# ProPrj_MSP3507__2025-07-14_10-12-05_2025.net
KiCad netlist of a schematic drawn in EasyEDA Pro
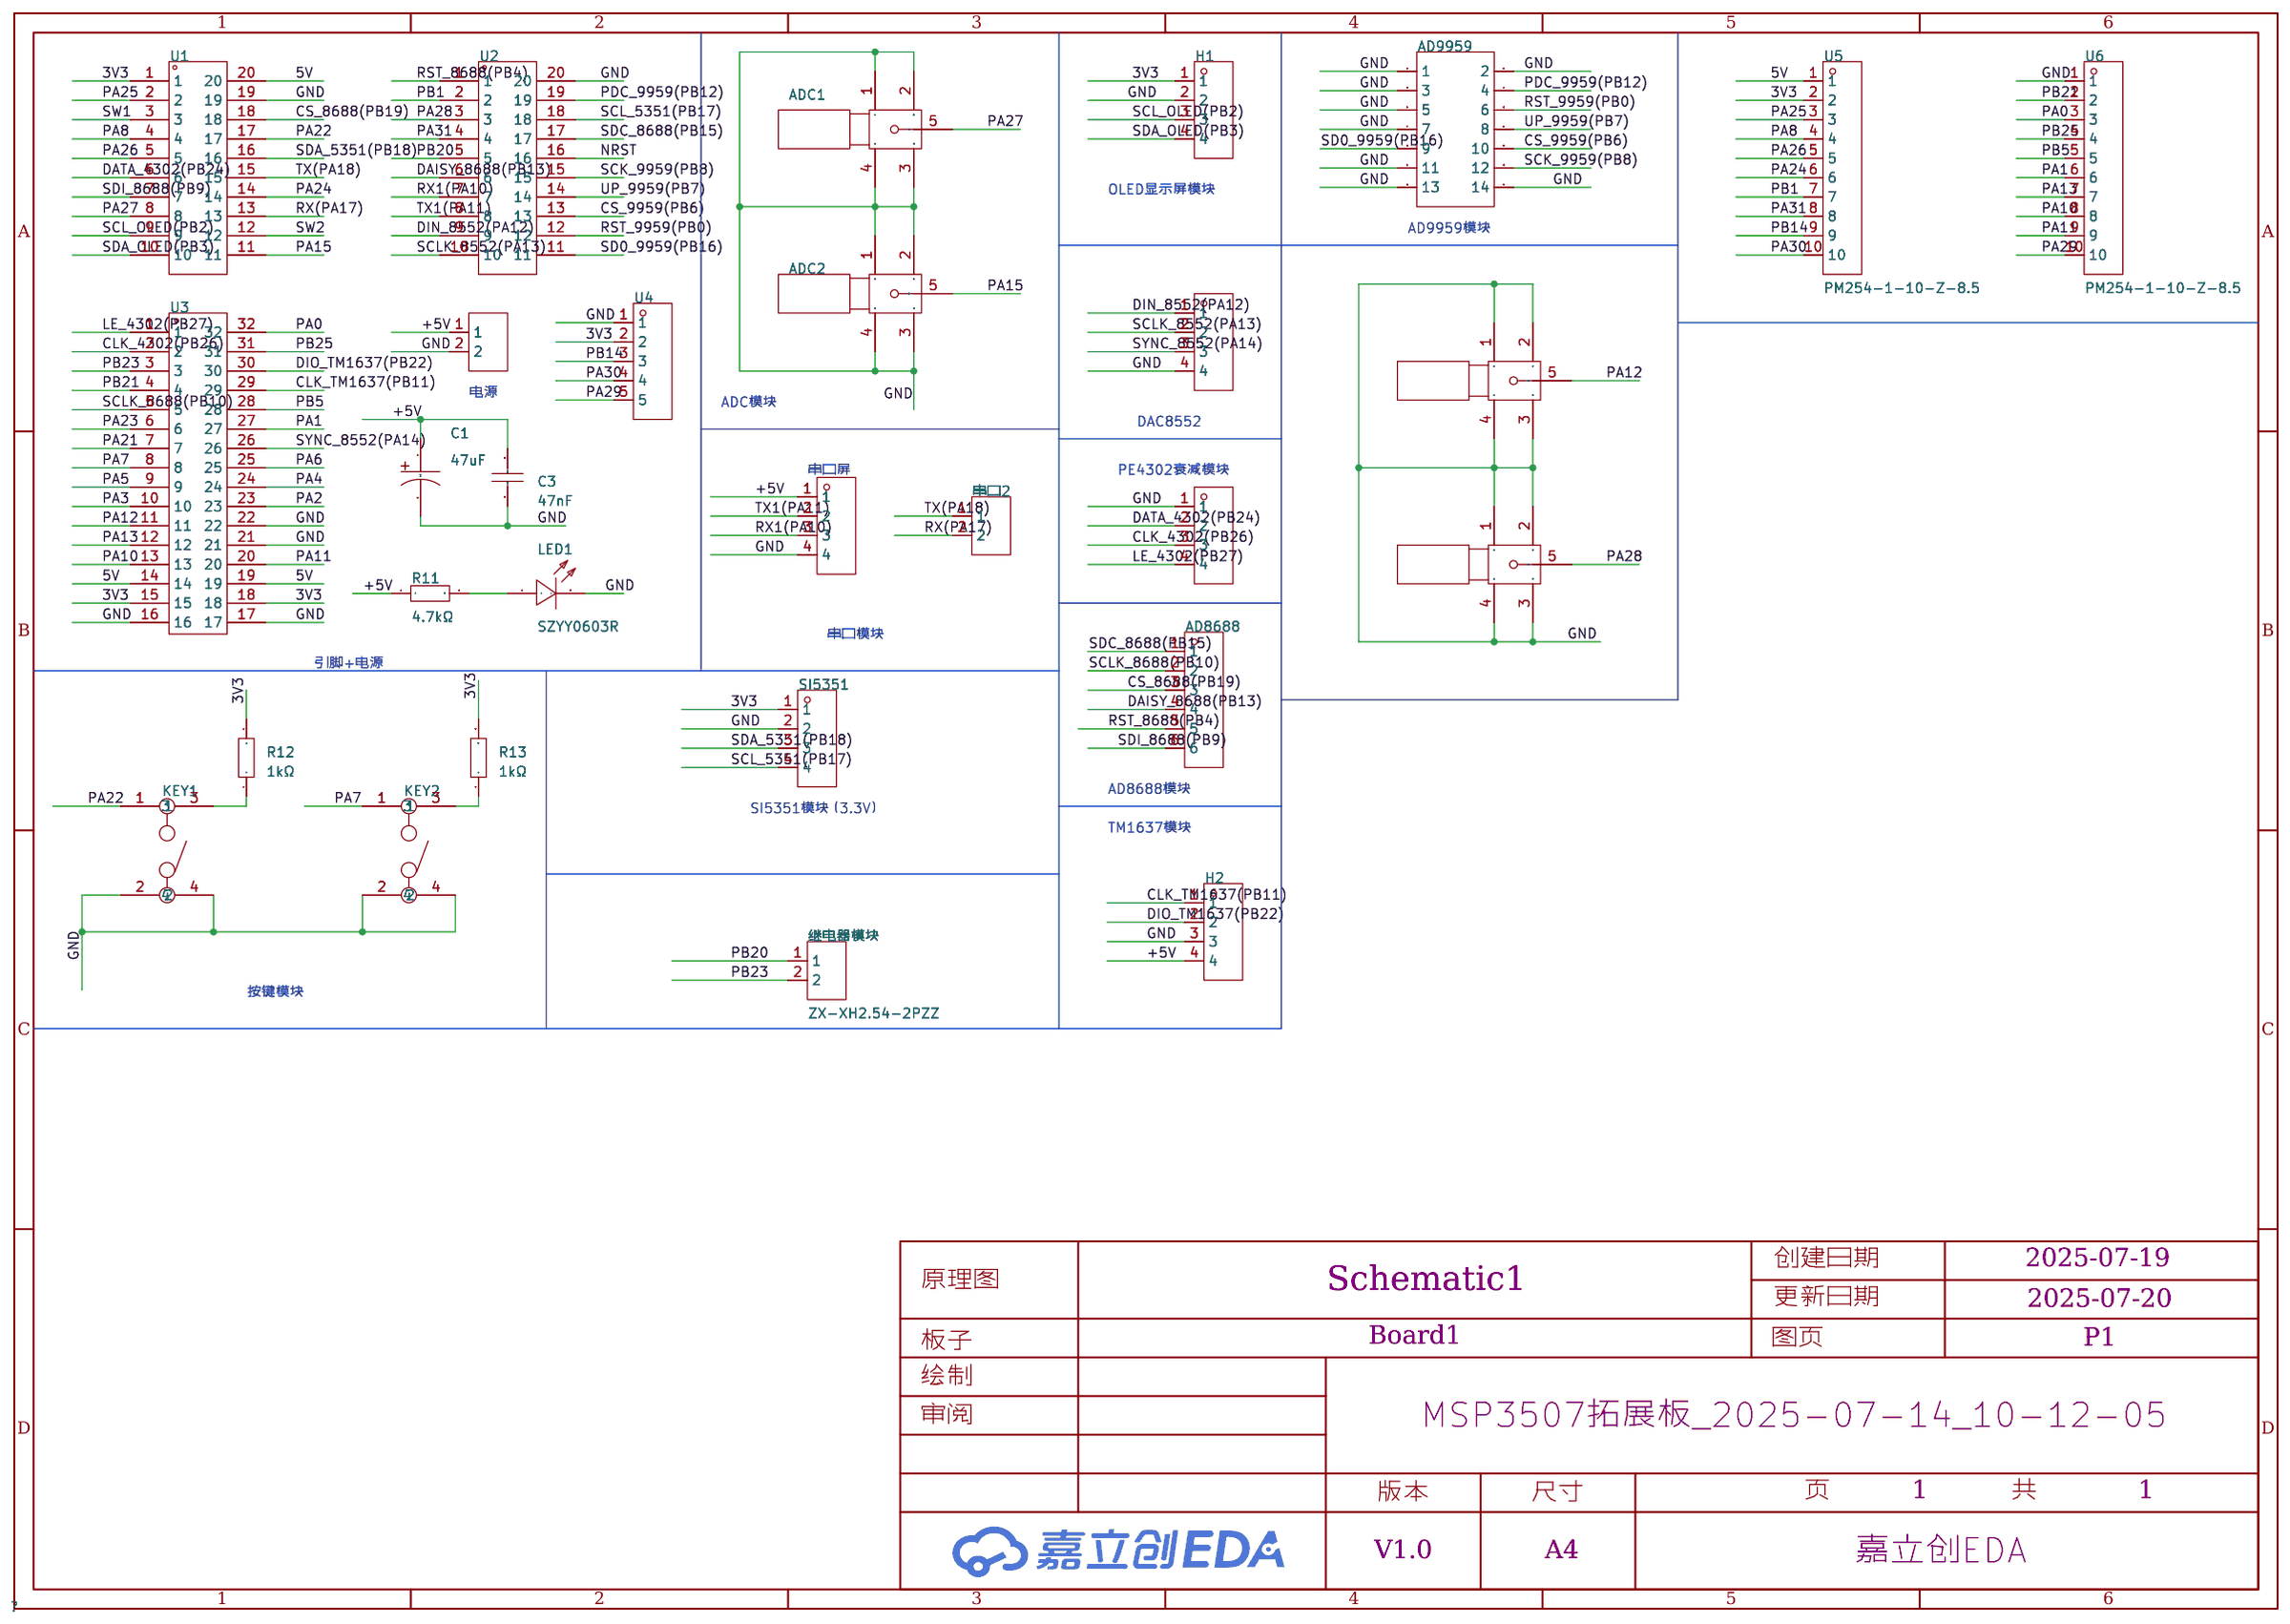
[diagram p0: schematic sheet]

(export (version "E")
  (design (tool "Eeschema 10.0.6"))
  (components
    (comp (ref "AD8688")
      (value "ZX-XH2.54-6PZZ")
      (footprint "easyedapro:CONN-TH_6P-P2.50_ZX-XH2.54-6PZZ")
      (fields (field (name "Manufacturer") "Megastar(兆星)"))
      (libsource (lib "easyedapro") (part "ZX-XH2.54-6PZZ"))
    )
    (comp (ref "AD9959")
      (value "2.54-2*7P简牛")
      (footprint "easyedapro:IDC-TH_14P-P2.54-V-R2-C7-S2.54")
      (description "连接器类型:简牛座;间距:2.54mm;结构:2x7P;封装形式:直插;行距:2.54mm;排数:2;每排PIN数:7;触头材质:黄铜;触头镀层:金;")
      (fields (field (name "Manufacturer") "BOOMELE(博穆精密)"))
      (libsource (lib "easyedapro") (part "HDR-IDC-2.54-2X7P"))
    )
    (comp (ref "ADC1")
      (value "BWSMA-KE-P001")
      (footprint "easyedapro:SMA-SMD_BWSMA-KE-P001")
      (description "连接器类型:板端;接口类型:内孔;端口数量:1;接口直径:5.2mm;接口长度/高度:-;频率-最大值:-;射频系列:SMA;阻抗:50Ω;样式:偏脚;工作温度范围:-;")
      (fields (field (name "Manufacturer") "BAT WIRELESS(蝙蝠无线)"))
      (libsource (lib "easyedapro") (part "BWSMA-KE-P001"))
    )
    (comp (ref "ADC2")
      (value "BWSMA-KE-P001")
      (footprint "easyedapro:SMA-SMD_BWSMA-KE-P001")
      (description "连接器类型:板端;接口类型:内孔;端口数量:1;接口直径:5.2mm;接口长度/高度:-;频率-最大值:-;射频系列:SMA;阻抗:50Ω;样式:偏脚;工作温度范围:-;")
      (fields (field (name "Manufacturer") "BAT WIRELESS(蝙蝠无线)"))
      (libsource (lib "easyedapro") (part "BWSMA-KE-P001"))
    )
    (comp (ref "C1")
      (value "47uF")
      (footprint "easyedapro:CAP-TH_BD5.0-P2.00-D0.8-FD")
      (description "容值:47uF;精度:±20%;额定电压:25V;纹波电流:250mA@100kHz;等效串联电阻(ESR):300mΩ@100kHz;")
      (fields
        (field (name "Manufacturer Part") "NXB25V47M5*11 2.5TP")
        (field (name "Manufacturer") "SAMYOUNG(韩国三莹)")
      )
      (libsource (lib "easyedapro") (part "NXB25VB47M5*11_2.5TP"))
    )
    (comp (ref "C3")
      (value "47nF")
      (footprint "easyedapro:C0805")
      (description "容值:47nF;精度:±10%;额定电压:50V;材质(温度系数):X7R;")
      (fields
        (field (name "Manufacturer Part") "CL21B473KBCNNNC")
        (field (name "Manufacturer") "SAMSUNG(三星)")
      )
      (libsource (lib "easyedapro") (part "CL21B473KBCNNNC"))
    )
    (comp (ref "DAC1")
      (value "BWSMA-KE-P001")
      (footprint "easyedapro:SMA-SMD_BWSMA-KE-P001")
      (description "连接器类型:板端;接口类型:内孔;端口数量:1;接口直径:5.2mm;接口长度/高度:-;频率-最大值:-;射频系列:SMA;阻抗:50Ω;样式:偏脚;工作温度范围:-;")
      (fields (field (name "Manufacturer") "BAT WIRELESS(蝙蝠无线)"))
      (libsource (lib "easyedapro") (part "BWSMA-KE-P001"))
    )
    (comp (ref "DAC2")
      (value "BWSMA-KE-P001")
      (footprint "easyedapro:SMA-SMD_BWSMA-KE-P001")
      (description "连接器类型:板端;接口类型:内孔;端口数量:1;接口直径:5.2mm;接口长度/高度:-;频率-最大值:-;射频系列:SMA;阻抗:50Ω;样式:偏脚;工作温度范围:-;")
      (fields (field (name "Manufacturer") "BAT WIRELESS(蝙蝠无线)"))
      (libsource (lib "easyedapro") (part "BWSMA-KE-P001"))
    )
    (comp (ref "H1")
      (value "~")
      (footprint "easyedapro:HDR-TH_4P-P2.54-V-F")
      (libsource (lib "easyedapro") (part "2.54-1*4P母"))
    )
    (comp (ref "H2")
      (value "~")
      (footprint "easyedapro:HDR-TH_4P-P2.54-V-F")
      (libsource (lib "easyedapro") (part "2.54-1*4P母"))
    )
    (comp (ref "KEY1")
      (value "~")
      (footprint "easyedapro:4角直插式开关")
      (description "4.5*4.5*3.8")
      (libsource (lib "easyedapro") (part "4角直插式开关"))
    )
    (comp (ref "KEY2")
      (value "~")
      (footprint "easyedapro:4角直插式开关")
      (description "4.5*4.5*3.8")
      (libsource (lib "easyedapro") (part "4角直插式开关"))
    )
    (comp (ref "LED1")
      (value "SZYY0603R")
      (footprint "easyedapro:LED0603-R-RD")
      (fields (field (name "Manufacturer") "yongyu(永裕光电)"))
      (libsource (lib "easyedapro") (part "SZYY0603R"))
    )
    (comp (ref "OLED显示屏模块1")
      (value "ZX-XH2.54-4PZZ")
      (footprint "easyedapro:CONN-TH_4P-P2.50_4PIN")
      (fields (field (name "Manufacturer") "Megastar(兆星)"))
      (libsource (lib "easyedapro") (part "ZX-XH2.54-4PZZ"))
    )
    (comp (ref "OLED显示屏模块2")
      (value "ZX-XH2.54-4PZZ")
      (footprint "easyedapro:CONN-TH_4P-P2.50_4PIN")
      (fields (field (name "Manufacturer") "Megastar(兆星)"))
      (libsource (lib "easyedapro") (part "ZX-XH2.54-4PZZ"))
    )
    (comp (ref "OLED显示屏模块3")
      (value "ZX-XH2.54-4PZZ")
      (footprint "easyedapro:CONN-TH_4P-P2.50_4PIN")
      (fields (field (name "Manufacturer") "Megastar(兆星)"))
      (libsource (lib "easyedapro") (part "ZX-XH2.54-4PZZ"))
    )
    (comp (ref "R11")
      (value "4.7kΩ")
      (footprint "easyedapro:R0805")
      (description "电阻类型:厚膜电阻;阻值:4.7kΩ;精度:±1%;功率:125mW;最大工作电压:150V;温度系数:±100ppm/°C;")
      (fields
        (field (name "Manufacturer Part") "0805W8F4701T5E")
        (field (name "Manufacturer") "UNI-ROYAL(厚声)")
      )
      (libsource (lib "easyedapro") (part "0805W8F4701T5E"))
    )
    (comp (ref "R12")
      (value "1kΩ")
      (footprint "easyedapro:R0805")
      (description "电阻类型:厚膜电阻;阻值:1kΩ;精度:±1%;功率:125mW;温度系数:±100ppm/°C;最大工作电压:150V;工作温度范围:-55°C~+155°C;")
      (fields
        (field (name "Manufacturer Part") "0805W8F1001T5E")
        (field (name "Manufacturer") "UNI-ROYAL(厚声)")
      )
      (libsource (lib "easyedapro") (part "0805W8F1001T5E"))
    )
    (comp (ref "R13")
      (value "1kΩ")
      (footprint "easyedapro:R0805")
      (description "电阻类型:厚膜电阻;阻值:1kΩ;精度:±1%;功率:125mW;温度系数:±100ppm/°C;最大工作电压:150V;工作温度范围:-55°C~+155°C;")
      (fields
        (field (name "Manufacturer Part") "0805W8F1001T5E")
        (field (name "Manufacturer") "UNI-ROYAL(厚声)")
      )
      (libsource (lib "easyedapro") (part "0805W8F1001T5E"))
    )
    (comp (ref "SI5351")
      (value "ZX-XH2.54-4PZZ")
      (footprint "easyedapro:CONN-TH_4P-P2.50_4PIN")
      (fields (field (name "Manufacturer") "Megastar(兆星)"))
      (libsource (lib "easyedapro") (part "ZX-XH2.54-4PZZ"))
    )
    (comp (ref "U1")
      (value "~")
      (footprint "easyedapro:2*10Pin排针")
      (description "2.54")
      (libsource (lib "easyedapro") (part "2*10Pin排针"))
    )
    (comp (ref "U2")
      (value "~")
      (footprint "easyedapro:2*10Pin排针")
      (description "2.54")
      (libsource (lib "easyedapro") (part "2*10Pin排针"))
    )
    (comp (ref "U3")
      (value "~")
      (footprint "easyedapro:2*16Pin排针")
      (description "2.54")
      (libsource (lib "easyedapro") (part "2*16Pin排针"))
    )
    (comp (ref "U4")
      (value "PZ254V-11-05P")
      (footprint "easyedapro:HDR-TH_5P-P2.54-V-M")
      (fields (field (name "Manufacturer") "XFCN(兴飞)"))
      (libsource (lib "easyedapro") (part "PZ254V-11-05P"))
    )
    (comp (ref "U5")
      (value "PM254-1-10-Z-8.5")
      (footprint "easyedapro:HDR-TH_10P-P2.54-V-F")
      (fields (field (name "Manufacturer") "HCTL(华灿天禄)"))
      (libsource (lib "easyedapro") (part "PM254-1-10-Z-8.5"))
    )
    (comp (ref "U6")
      (value "PM254-1-10-Z-8.5")
      (footprint "easyedapro:HDR-TH_10P-P2.54-V-F")
      (fields (field (name "Manufacturer") "HCTL(华灿天禄)"))
      (libsource (lib "easyedapro") (part "PM254-1-10-Z-8.5"))
    )
    (comp (ref "串口1")
      (value "ZX-XH2.54-2PZZ")
      (footprint "easyedapro:CONN-TH_2P-P2.50_HX25003-2A")
      (fields (field (name "Manufacturer") "Megastar(兆星)"))
      (libsource (lib "easyedapro") (part "ZX-XH2.54-2PZZ"))
    )
    (comp (ref "串口2")
      (value "ZX-XH2.54-2PZZ")
      (footprint "easyedapro:CONN-TH_2P-P2.50_HX25003-2A")
      (fields (field (name "Manufacturer") "Megastar(兆星)"))
      (libsource (lib "easyedapro") (part "ZX-XH2.54-2PZZ"))
    )
    (comp (ref "继电器模块")
      (value "ZX-XH2.54-2PZZ")
      (footprint "easyedapro:CONN-TH_2P-P2.50_HX25003-2A")
      (fields (field (name "Manufacturer") "Megastar(兆星)"))
      (libsource (lib "easyedapro") (part "ZX-XH2.54-2PZZ"))
    )
  )
  (nets
    (net (code "1") (name "/+5V") (class "Default")
      (node (ref "C1") (pin "1") (pinfunction "1_1") (pintype "unspecified"))
      (node (ref "C3") (pin "2") (pinfunction "2_2") (pintype "input"))
      (node (ref "H2") (pin "4") (pinfunction "4_4") (pintype "unspecified"))
      (node (ref "OLED显示屏模块2") (pin "1") (pinfunction "1_1") (pintype "unspecified"))
      (node (ref "R11") (pin "1") (pinfunction "1_1") (pintype "input"))
      (node (ref "串口1") (pin "1") (pinfunction "1_1") (pintype "unspecified"))
    )
    (net (code "2") (name "/3V3") (class "Default")
      (node (ref "H1") (pin "1") (pinfunction "1_1") (pintype "unspecified"))
      (node (ref "R12") (pin "2") (pinfunction "2_2") (pintype "input"))
      (node (ref "R13") (pin "2") (pinfunction "2_2") (pintype "input"))
      (node (ref "SI5351") (pin "1") (pinfunction "1_1") (pintype "unspecified"))
      (node (ref "U1") (pin "1") (pinfunction "1_1") (pintype "input"))
      (node (ref "U3") (pin "15") (pinfunction "15_15") (pintype "input"))
      (node (ref "U3") (pin "18") (pinfunction "18_18") (pintype "input"))
      (node (ref "U4") (pin "2") (pinfunction "2_2") (pintype "input"))
      (node (ref "U5") (pin "2") (pinfunction "2_2") (pintype "unspecified"))
    )
    (net (code "3") (name "/5V") (class "Default")
      (node (ref "U1") (pin "20") (pinfunction "20_20") (pintype "input"))
      (node (ref "U3") (pin "14") (pinfunction "14_14") (pintype "input"))
      (node (ref "U3") (pin "19") (pinfunction "19_19") (pintype "input"))
      (node (ref "U5") (pin "1") (pinfunction "1_1") (pintype "unspecified"))
    )
    (net (code "4") (name "/CLK_4302(PB26)") (class "Default")
      (node (ref "OLED显示屏模块1") (pin "3") (pinfunction "3_3") (pintype "unspecified"))
      (node (ref "U3") (pin "2") (pinfunction "2_2") (pintype "input"))
    )
    (net (code "5") (name "/CLK_TM1637(PB11)") (class "Default")
      (node (ref "H2") (pin "1") (pinfunction "1_1") (pintype "unspecified"))
      (node (ref "U3") (pin "29") (pinfunction "29_29") (pintype "input"))
    )
    (net (code "6") (name "/CS_8688(PB19)") (class "Default")
      (node (ref "AD8688") (pin "3") (pinfunction "3_3") (pintype "unspecified"))
      (node (ref "U1") (pin "18") (pinfunction "18_18") (pintype "input"))
    )
    (net (code "7") (name "/CS_9959(PB6)") (class "Default")
      (node (ref "AD9959") (pin "10") (pinfunction "10_10") (pintype "unspecified"))
      (node (ref "U2") (pin "13") (pinfunction "13_13") (pintype "input"))
    )
    (net (code "8") (name "/DAISY_8688(PB13)") (class "Default")
      (node (ref "AD8688") (pin "4") (pinfunction "4_4") (pintype "unspecified"))
      (node (ref "U2") (pin "6") (pinfunction "6_6") (pintype "input"))
    )
    (net (code "9") (name "/DATA_4302(PB24)") (class "Default")
      (node (ref "OLED显示屏模块1") (pin "2") (pinfunction "2_2") (pintype "unspecified"))
      (node (ref "U1") (pin "6") (pinfunction "6_6") (pintype "input"))
    )
    (net (code "10") (name "/DIN_8552(PA12)") (class "Default")
      (node (ref "OLED显示屏模块3") (pin "1") (pinfunction "1_1") (pintype "unspecified"))
      (node (ref "U2") (pin "9") (pinfunction "9_9") (pintype "input"))
    )
    (net (code "11") (name "/DIO_TM1637(PB22)") (class "Default")
      (node (ref "H2") (pin "2") (pinfunction "2_2") (pintype "unspecified"))
      (node (ref "U3") (pin "30") (pinfunction "30_30") (pintype "input"))
    )
    (net (code "12") (name "/GND") (class "Default")
      (node (ref "AD9959") (pin "1") (pinfunction "1_1") (pintype "unspecified"))
      (node (ref "AD9959") (pin "11") (pinfunction "11_11") (pintype "unspecified"))
      (node (ref "AD9959") (pin "13") (pinfunction "13_13") (pintype "unspecified"))
      (node (ref "AD9959") (pin "14") (pinfunction "14_14") (pintype "unspecified"))
      (node (ref "AD9959") (pin "2") (pinfunction "2_2") (pintype "unspecified"))
      (node (ref "AD9959") (pin "3") (pinfunction "3_3") (pintype "unspecified"))
      (node (ref "AD9959") (pin "5") (pinfunction "5_5") (pintype "unspecified"))
      (node (ref "AD9959") (pin "7") (pinfunction "7_7") (pintype "unspecified"))
      (node (ref "ADC1") (pin "1") (pinfunction "1_1") (pintype "unspecified"))
      (node (ref "ADC1") (pin "2") (pinfunction "2_2") (pintype "unspecified"))
      (node (ref "ADC1") (pin "3") (pinfunction "3_3") (pintype "unspecified"))
      (node (ref "ADC1") (pin "4") (pinfunction "4_4") (pintype "unspecified"))
      (node (ref "ADC2") (pin "1") (pinfunction "1_1") (pintype "unspecified"))
      (node (ref "ADC2") (pin "2") (pinfunction "2_2") (pintype "unspecified"))
      (node (ref "ADC2") (pin "3") (pinfunction "3_3") (pintype "unspecified"))
      (node (ref "ADC2") (pin "4") (pinfunction "4_4") (pintype "unspecified"))
      (node (ref "C1") (pin "2") (pinfunction "2_2") (pintype "unspecified"))
      (node (ref "C3") (pin "1") (pinfunction "1_1") (pintype "input"))
      (node (ref "DAC1") (pin "1") (pinfunction "1_1") (pintype "unspecified"))
      (node (ref "DAC1") (pin "2") (pinfunction "2_2") (pintype "unspecified"))
      (node (ref "DAC1") (pin "3") (pinfunction "3_3") (pintype "unspecified"))
      (node (ref "DAC1") (pin "4") (pinfunction "4_4") (pintype "unspecified"))
      (node (ref "DAC2") (pin "1") (pinfunction "1_1") (pintype "unspecified"))
      (node (ref "DAC2") (pin "2") (pinfunction "2_2") (pintype "unspecified"))
      (node (ref "DAC2") (pin "3") (pinfunction "3_3") (pintype "unspecified"))
      (node (ref "DAC2") (pin "4") (pinfunction "4_4") (pintype "unspecified"))
      (node (ref "H1") (pin "2") (pinfunction "2_2") (pintype "unspecified"))
      (node (ref "H2") (pin "3") (pinfunction "3_3") (pintype "unspecified"))
      (node (ref "KEY1") (pin "2") (pinfunction "2_2") (pintype "input"))
      (node (ref "KEY1") (pin "4") (pinfunction "4_4") (pintype "input"))
      (node (ref "KEY2") (pin "2") (pinfunction "2_2") (pintype "input"))
      (node (ref "KEY2") (pin "4") (pinfunction "4_4") (pintype "input"))
      (node (ref "LED1") (pin "2") (pinfunction "-_2") (pintype "unspecified"))
      (node (ref "OLED显示屏模块1") (pin "1") (pinfunction "1_1") (pintype "unspecified"))
      (node (ref "OLED显示屏模块2") (pin "4") (pinfunction "4_4") (pintype "unspecified"))
      (node (ref "OLED显示屏模块3") (pin "4") (pinfunction "4_4") (pintype "unspecified"))
      (node (ref "SI5351") (pin "2") (pinfunction "2_2") (pintype "unspecified"))
      (node (ref "U1") (pin "19") (pinfunction "19_19") (pintype "input"))
      (node (ref "U2") (pin "20") (pinfunction "20_20") (pintype "input"))
      (node (ref "U3") (pin "16") (pinfunction "16_16") (pintype "input"))
      (node (ref "U3") (pin "17") (pinfunction "17_17") (pintype "input"))
      (node (ref "U3") (pin "21") (pinfunction "21_21") (pintype "input"))
      (node (ref "U3") (pin "22") (pinfunction "22_22") (pintype "input"))
      (node (ref "U4") (pin "1") (pinfunction "1_1") (pintype "input"))
      (node (ref "U6") (pin "1") (pinfunction "1_1") (pintype "unspecified"))
      (node (ref "串口1") (pin "2") (pinfunction "2_2") (pintype "unspecified"))
    )
    (net (code "13") (name "/LE_4302(PB27)") (class "Default")
      (node (ref "OLED显示屏模块1") (pin "4") (pinfunction "4_4") (pintype "unspecified"))
      (node (ref "U3") (pin "1") (pinfunction "1_1") (pintype "input"))
    )
    (net (code "14") (name "/NRST") (class "Default")
      (node (ref "U2") (pin "16") (pinfunction "16_16") (pintype "input"))
    )
    (net (code "15") (name "/PA0") (class "Default")
      (node (ref "U3") (pin "32") (pinfunction "32_32") (pintype "input"))
      (node (ref "U6") (pin "3") (pinfunction "3_3") (pintype "unspecified"))
    )
    (net (code "16") (name "/PA1") (class "Default")
      (node (ref "U3") (pin "27") (pinfunction "27_27") (pintype "input"))
      (node (ref "U6") (pin "6") (pinfunction "6_6") (pintype "unspecified"))
    )
    (net (code "17") (name "/PA2") (class "Default")
      (node (ref "U3") (pin "23") (pinfunction "23_23") (pintype "input"))
    )
    (net (code "18") (name "/PA3") (class "Default")
      (node (ref "U3") (pin "10") (pinfunction "10_10") (pintype "input"))
    )
    (net (code "19") (name "/PA4") (class "Default")
      (node (ref "U3") (pin "24") (pinfunction "24_24") (pintype "input"))
    )
    (net (code "20") (name "/PA5") (class "Default")
      (node (ref "U3") (pin "9") (pinfunction "9_9") (pintype "input"))
    )
    (net (code "21") (name "/PA6") (class "Default")
      (node (ref "U3") (pin "25") (pinfunction "25_25") (pintype "input"))
    )
    (net (code "22") (name "/PA7") (class "Default")
      (node (ref "KEY2") (pin "1") (pinfunction "1_1") (pintype "input"))
      (node (ref "U3") (pin "8") (pinfunction "8_8") (pintype "input"))
    )
    (net (code "23") (name "/PA8") (class "Default")
      (node (ref "U1") (pin "4") (pinfunction "4_4") (pintype "input"))
      (node (ref "U5") (pin "4") (pinfunction "4_4") (pintype "unspecified"))
    )
    (net (code "24") (name "/PA10") (class "Default")
      (node (ref "U3") (pin "13") (pinfunction "13_13") (pintype "input"))
      (node (ref "U6") (pin "8") (pinfunction "8_8") (pintype "unspecified"))
    )
    (net (code "25") (name "/PA11") (class "Default")
      (node (ref "U3") (pin "20") (pinfunction "20_20") (pintype "input"))
      (node (ref "U6") (pin "9") (pinfunction "9_9") (pintype "unspecified"))
    )
    (net (code "26") (name "/PA12") (class "Default")
      (node (ref "DAC1") (pin "5") (pinfunction "5_5") (pintype "unspecified"))
      (node (ref "U3") (pin "11") (pinfunction "11_11") (pintype "input"))
    )
    (net (code "27") (name "/PA13") (class "Default")
      (node (ref "U3") (pin "12") (pinfunction "12_12") (pintype "input"))
      (node (ref "U6") (pin "7") (pinfunction "7_7") (pintype "unspecified"))
    )
    (net (code "28") (name "/PA15") (class "Default")
      (node (ref "ADC2") (pin "5") (pinfunction "5_5") (pintype "unspecified"))
      (node (ref "U1") (pin "11") (pinfunction "11_11") (pintype "input"))
    )
    (net (code "29") (name "/PA21") (class "Default")
      (node (ref "U3") (pin "7") (pinfunction "7_7") (pintype "input"))
    )
    (net (code "30") (name "/PA22") (class "Default")
      (node (ref "KEY1") (pin "1") (pinfunction "1_1") (pintype "input"))
      (node (ref "U1") (pin "17") (pinfunction "17_17") (pintype "input"))
    )
    (net (code "31") (name "/PA23") (class "Default")
      (node (ref "U3") (pin "6") (pinfunction "6_6") (pintype "input"))
    )
    (net (code "32") (name "/PA24") (class "Default")
      (node (ref "U1") (pin "14") (pinfunction "14_14") (pintype "input"))
      (node (ref "U5") (pin "6") (pinfunction "6_6") (pintype "unspecified"))
    )
    (net (code "33") (name "/PA25") (class "Default")
      (node (ref "U1") (pin "2") (pinfunction "2_2") (pintype "input"))
      (node (ref "U5") (pin "3") (pinfunction "3_3") (pintype "unspecified"))
    )
    (net (code "34") (name "/PA26") (class "Default")
      (node (ref "U1") (pin "5") (pinfunction "5_5") (pintype "input"))
      (node (ref "U5") (pin "5") (pinfunction "5_5") (pintype "unspecified"))
    )
    (net (code "35") (name "/PA27") (class "Default")
      (node (ref "ADC1") (pin "5") (pinfunction "5_5") (pintype "unspecified"))
      (node (ref "U1") (pin "8") (pinfunction "8_8") (pintype "input"))
    )
    (net (code "36") (name "/PA28") (class "Default")
      (node (ref "DAC2") (pin "5") (pinfunction "5_5") (pintype "unspecified"))
      (node (ref "U2") (pin "3") (pinfunction "3_3") (pintype "input"))
    )
    (net (code "37") (name "/PA29") (class "Default")
      (node (ref "U4") (pin "5") (pinfunction "5_5") (pintype "input"))
      (node (ref "U6") (pin "10") (pinfunction "10_10") (pintype "unspecified"))
    )
    (net (code "38") (name "/PA30") (class "Default")
      (node (ref "U4") (pin "4") (pinfunction "4_4") (pintype "input"))
      (node (ref "U5") (pin "10") (pinfunction "10_10") (pintype "unspecified"))
    )
    (net (code "39") (name "/PA31") (class "Default")
      (node (ref "U2") (pin "4") (pinfunction "4_4") (pintype "input"))
      (node (ref "U5") (pin "8") (pinfunction "8_8") (pintype "unspecified"))
    )
    (net (code "40") (name "/PB1") (class "Default")
      (node (ref "U2") (pin "2") (pinfunction "2_2") (pintype "input"))
      (node (ref "U5") (pin "7") (pinfunction "7_7") (pintype "unspecified"))
    )
    (net (code "41") (name "/PB5") (class "Default")
      (node (ref "U3") (pin "28") (pinfunction "28_28") (pintype "input"))
      (node (ref "U6") (pin "5") (pinfunction "5_5") (pintype "unspecified"))
    )
    (net (code "42") (name "/PB14") (class "Default")
      (node (ref "U4") (pin "3") (pinfunction "3_3") (pintype "input"))
      (node (ref "U5") (pin "9") (pinfunction "9_9") (pintype "unspecified"))
    )
    (net (code "43") (name "/PB20") (class "Default")
      (node (ref "U2") (pin "5") (pinfunction "5_5") (pintype "input"))
      (node (ref "继电器模块") (pin "1") (pinfunction "1_1") (pintype "unspecified"))
    )
    (net (code "44") (name "/PB21") (class "Default")
      (node (ref "U3") (pin "4") (pinfunction "4_4") (pintype "input"))
      (node (ref "U6") (pin "2") (pinfunction "2_2") (pintype "unspecified"))
    )
    (net (code "45") (name "/PB23") (class "Default")
      (node (ref "U3") (pin "3") (pinfunction "3_3") (pintype "input"))
      (node (ref "继电器模块") (pin "2") (pinfunction "2_2") (pintype "unspecified"))
    )
    (net (code "46") (name "/PB25") (class "Default")
      (node (ref "U3") (pin "31") (pinfunction "31_31") (pintype "input"))
      (node (ref "U6") (pin "4") (pinfunction "4_4") (pintype "unspecified"))
    )
    (net (code "47") (name "/PDC_9959(PB12)") (class "Default")
      (node (ref "AD9959") (pin "4") (pinfunction "4_4") (pintype "unspecified"))
      (node (ref "U2") (pin "19") (pinfunction "19_19") (pintype "input"))
    )
    (net (code "48") (name "/RST_8688(PB4)") (class "Default")
      (node (ref "AD8688") (pin "5") (pinfunction "5_5") (pintype "unspecified"))
      (node (ref "U2") (pin "1") (pinfunction "1_1") (pintype "input"))
    )
    (net (code "49") (name "/RST_9959(PB0)") (class "Default")
      (node (ref "AD9959") (pin "6") (pinfunction "6_6") (pintype "unspecified"))
      (node (ref "U2") (pin "12") (pinfunction "12_12") (pintype "input"))
    )
    (net (code "50") (name "/RX(PA17)") (class "Default")
      (node (ref "U1") (pin "13") (pinfunction "13_13") (pintype "input"))
      (node (ref "串口2") (pin "2") (pinfunction "2_2") (pintype "unspecified"))
    )
    (net (code "51") (name "/RX1(PA10)") (class "Default")
      (node (ref "OLED显示屏模块2") (pin "3") (pinfunction "3_3") (pintype "unspecified"))
      (node (ref "U2") (pin "7") (pinfunction "7_7") (pintype "input"))
    )
    (net (code "52") (name "/SCK_9959(PB8)") (class "Default")
      (node (ref "AD9959") (pin "12") (pinfunction "12_12") (pintype "unspecified"))
      (node (ref "U2") (pin "15") (pinfunction "15_15") (pintype "input"))
    )
    (net (code "53") (name "/SCLK_8552(PA13)") (class "Default")
      (node (ref "OLED显示屏模块3") (pin "2") (pinfunction "2_2") (pintype "unspecified"))
      (node (ref "U2") (pin "10") (pinfunction "10_10") (pintype "input"))
    )
    (net (code "54") (name "/SCLK_8688(PB10)") (class "Default")
      (node (ref "AD8688") (pin "2") (pinfunction "2_2") (pintype "unspecified"))
      (node (ref "U3") (pin "5") (pinfunction "5_5") (pintype "input"))
    )
    (net (code "55") (name "/SCL_5351(PB17)") (class "Default")
      (node (ref "SI5351") (pin "4") (pinfunction "4_4") (pintype "unspecified"))
      (node (ref "U2") (pin "18") (pinfunction "18_18") (pintype "input"))
    )
    (net (code "56") (name "/SCL_OLED(PB2)") (class "Default")
      (node (ref "H1") (pin "3") (pinfunction "3_3") (pintype "unspecified"))
      (node (ref "U1") (pin "9") (pinfunction "9_9") (pintype "input"))
    )
    (net (code "57") (name "/SD0_9959(PB16)") (class "Default")
      (node (ref "AD9959") (pin "9") (pinfunction "9_9") (pintype "unspecified"))
      (node (ref "U2") (pin "11") (pinfunction "11_11") (pintype "input"))
    )
    (net (code "58") (name "/SDA_5351(PB18)") (class "Default")
      (node (ref "SI5351") (pin "3") (pinfunction "3_3") (pintype "unspecified"))
      (node (ref "U1") (pin "16") (pinfunction "16_16") (pintype "input"))
    )
    (net (code "59") (name "/SDA_OLED(PB3)") (class "Default")
      (node (ref "H1") (pin "4") (pinfunction "4_4") (pintype "unspecified"))
      (node (ref "U1") (pin "10") (pinfunction "10_10") (pintype "input"))
    )
    (net (code "60") (name "/SDC_8688(PB15)") (class "Default")
      (node (ref "AD8688") (pin "1") (pinfunction "1_1") (pintype "unspecified"))
      (node (ref "U2") (pin "17") (pinfunction "17_17") (pintype "input"))
    )
    (net (code "61") (name "/SDI_8688(PB9)") (class "Default")
      (node (ref "AD8688") (pin "6") (pinfunction "6_6") (pintype "unspecified"))
      (node (ref "U1") (pin "7") (pinfunction "7_7") (pintype "input"))
    )
    (net (code "62") (name "/SW1") (class "Default")
      (node (ref "U1") (pin "3") (pinfunction "3_3") (pintype "input"))
    )
    (net (code "63") (name "/SW2") (class "Default")
      (node (ref "U1") (pin "12") (pinfunction "12_12") (pintype "input"))
    )
    (net (code "64") (name "/SYNC_8552(PA14)") (class "Default")
      (node (ref "OLED显示屏模块3") (pin "3") (pinfunction "3_3") (pintype "unspecified"))
      (node (ref "U3") (pin "26") (pinfunction "26_26") (pintype "input"))
    )
    (net (code "65") (name "/TX(PA18)") (class "Default")
      (node (ref "U1") (pin "15") (pinfunction "15_15") (pintype "input"))
      (node (ref "串口2") (pin "1") (pinfunction "1_1") (pintype "unspecified"))
    )
    (net (code "66") (name "/TX1(PA11)") (class "Default")
      (node (ref "OLED显示屏模块2") (pin "2") (pinfunction "2_2") (pintype "unspecified"))
      (node (ref "U2") (pin "8") (pinfunction "8_8") (pintype "input"))
    )
    (net (code "67") (name "/UP_9959(PB7)") (class "Default")
      (node (ref "AD9959") (pin "8") (pinfunction "8_8") (pintype "unspecified"))
      (node (ref "U2") (pin "14") (pinfunction "14_14") (pintype "input"))
    )
    (net (code "68") (name "Net-(KEY1-Pad3)") (class "Default")
      (node (ref "KEY1") (pin "3") (pinfunction "3_3") (pintype "input"))
      (node (ref "R12") (pin "1") (pinfunction "1_1") (pintype "input"))
    )
    (net (code "69") (name "Net-(KEY2-Pad3)") (class "Default")
      (node (ref "KEY2") (pin "3") (pinfunction "3_3") (pintype "input"))
      (node (ref "R13") (pin "1") (pinfunction "1_1") (pintype "input"))
    )
    (net (code "70") (name "Net-(LED1-+)") (class "Default")
      (node (ref "LED1") (pin "1") (pinfunction "+_1") (pintype "unspecified"))
      (node (ref "R11") (pin "2") (pinfunction "2_2") (pintype "input"))
    )
  )
)
